# HCF4051.net
KiCad netlist of a schematic drawn in Altium Designer
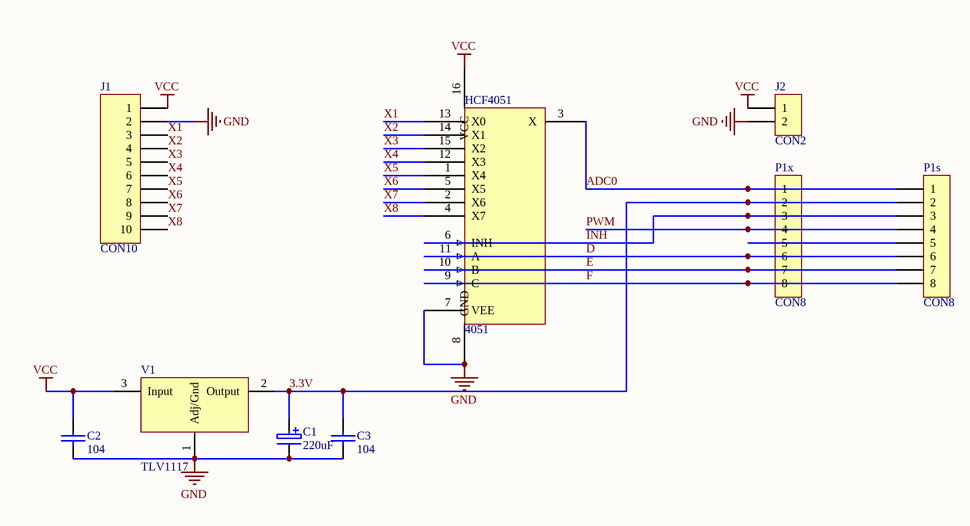
[diagram p0: HCF4051.SchDoc]

(export (version "E")
  (design (tool "Eeschema 10.0.6"))
  (components
    (comp (ref "C1") (value "220uF") (footprint "CAO1") (libsource (lib "C电容") (part "CAP3")))
    (comp (ref "C2") (value "104") (footprint "C0805") (libsource (lib "C电容") (part "CAP1")))
    (comp (ref "C3") (value "104") (footprint "C0805") (libsource (lib "C电容") (part "CAP1")))
    (comp (ref "HCF4051") (value "4051") (footprint "SOP-16") (libsource (lib "4000 CMOS") (part "4051")))
    (comp (ref "J1")
      (value "CON10")
      (footprint "sip-10")
      (description "Connector")
      (libsource (lib "接口") (part "CON10"))
    )
    (comp (ref "J2")
      (value "CON2")
      (footprint "sip-2")
      (description "Connector")
      (libsource (lib "接口") (part "CON2"))
    )
    (comp (ref "P1s")
      (value "CON8")
      (footprint "sip-8")
      (description "Connector")
      (libsource (lib "接口") (part "CON8"))
    )
    (comp (ref "P1x")
      (value "CON8")
      (footprint "sip-8")
      (description "Connector")
      (libsource (lib "接口") (part "CON8"))
    )
    (comp (ref "V1") (value "TLV1117") (footprint "SOT-223") (libsource (lib "Voltage电压基准") (part "TLV1117")))
  )
  (nets
    (net (code "1") (name "/3.3V") (class "Default")
      (node (ref "C1") (pin "1") (pintype "passive"))
      (node (ref "C3") (pin "2") (pinfunction "2_2") (pintype "passive"))
      (node (ref "P1s") (pin "2") (pinfunction "2_2") (pintype "passive"))
      (node (ref "P1x") (pin "2") (pinfunction "2_2") (pintype "passive"))
      (node (ref "V1") (pin "2") (pinfunction "Output_2") (pintype "passive"))
    )
    (net (code "2") (name "/ADC0") (class "Default")
      (node (ref "HCF4051") (pin "3") (pinfunction "X_3") (pintype "passive"))
      (node (ref "P1s") (pin "1") (pinfunction "1_1") (pintype "passive"))
      (node (ref "P1x") (pin "1") (pinfunction "1_1") (pintype "passive"))
    )
    (net (code "3") (name "/D") (class "Default")
      (node (ref "HCF4051") (pin "11") (pinfunction "A_11") (pintype "input"))
      (node (ref "P1s") (pin "6") (pinfunction "6_6") (pintype "passive"))
      (node (ref "P1x") (pin "6") (pinfunction "6_6") (pintype "passive"))
    )
    (net (code "4") (name "/E") (class "Default")
      (node (ref "HCF4051") (pin "10") (pinfunction "B_10") (pintype "input"))
      (node (ref "P1s") (pin "7") (pinfunction "7_7") (pintype "passive"))
      (node (ref "P1x") (pin "7") (pinfunction "7_7") (pintype "passive"))
    )
    (net (code "5") (name "/F") (class "Default")
      (node (ref "HCF4051") (pin "9") (pinfunction "C_9") (pintype "input"))
      (node (ref "P1s") (pin "8") (pinfunction "8_8") (pintype "passive"))
      (node (ref "P1x") (pin "8") (pinfunction "8_8") (pintype "passive"))
    )
    (net (code "6") (name "/INH") (class "Default")
      (node (ref "HCF4051") (pin "6") (pinfunction "INH_6") (pintype "input"))
      (node (ref "P1s") (pin "3") (pinfunction "3_3") (pintype "passive"))
      (node (ref "P1x") (pin "3") (pinfunction "3_3") (pintype "passive"))
    )
    (net (code "7") (name "/PWM") (class "Default")
      (node (ref "P1s") (pin "4") (pinfunction "4_4") (pintype "passive"))
      (node (ref "P1x") (pin "4") (pinfunction "4_4") (pintype "passive"))
    )
    (net (code "8") (name "/X1") (class "Default")
      (node (ref "HCF4051") (pin "13") (pinfunction "X0_13") (pintype "passive"))
      (node (ref "J1") (pin "3") (pinfunction "3_3") (pintype "passive"))
    )
    (net (code "9") (name "/X2") (class "Default")
      (node (ref "HCF4051") (pin "14") (pinfunction "X1_14") (pintype "passive"))
      (node (ref "J1") (pin "4") (pinfunction "4_4") (pintype "passive"))
    )
    (net (code "10") (name "/X3") (class "Default")
      (node (ref "HCF4051") (pin "15") (pinfunction "X2_15") (pintype "passive"))
      (node (ref "J1") (pin "5") (pinfunction "5_5") (pintype "passive"))
    )
    (net (code "11") (name "/X4") (class "Default")
      (node (ref "HCF4051") (pin "12") (pinfunction "X3_12") (pintype "passive"))
      (node (ref "J1") (pin "6") (pinfunction "6_6") (pintype "passive"))
    )
    (net (code "12") (name "/X5") (class "Default")
      (node (ref "HCF4051") (pin "1") (pinfunction "X4_1") (pintype "passive"))
      (node (ref "J1") (pin "7") (pinfunction "7_7") (pintype "passive"))
    )
    (net (code "13") (name "/X6") (class "Default")
      (node (ref "HCF4051") (pin "5") (pinfunction "X5_5") (pintype "passive"))
      (node (ref "J1") (pin "8") (pinfunction "8_8") (pintype "passive"))
    )
    (net (code "14") (name "/X7") (class "Default")
      (node (ref "HCF4051") (pin "2") (pinfunction "X6_2") (pintype "passive"))
      (node (ref "J1") (pin "9") (pinfunction "9_9") (pintype "passive"))
    )
    (net (code "15") (name "/X8") (class "Default")
      (node (ref "HCF4051") (pin "4") (pinfunction "X7_4") (pintype "passive"))
      (node (ref "J1") (pin "10") (pinfunction "10_10") (pintype "passive"))
    )
    (net (code "16") (name "GND") (class "Default")
      (node (ref "C1") (pin "2") (pintype "passive"))
      (node (ref "C2") (pin "1") (pinfunction "1_1") (pintype "passive"))
      (node (ref "C3") (pin "1") (pinfunction "1_1") (pintype "passive"))
      (node (ref "HCF4051") (pin "7") (pinfunction "VEE_7") (pintype "passive"))
      (node (ref "HCF4051") (pin "8") (pinfunction "GND_8") (pintype "power_in"))
      (node (ref "J1") (pin "2") (pinfunction "2_2") (pintype "passive"))
      (node (ref "J2") (pin "2") (pinfunction "2_2") (pintype "passive"))
      (node (ref "V1") (pin "1") (pinfunction "Adj/Gnd_1") (pintype "passive"))
    )
    (net (code "17") (name "Net-(P1s-Pad5)") (class "Default")
      (node (ref "P1s") (pin "5") (pinfunction "5_5") (pintype "passive"))
      (node (ref "P1x") (pin "5") (pinfunction "5_5") (pintype "passive"))
    )
    (net (code "18") (name "VCC") (class "Default")
      (node (ref "C2") (pin "2") (pinfunction "2_2") (pintype "passive"))
      (node (ref "HCF4051") (pin "16") (pinfunction "VCC_16") (pintype "power_in"))
      (node (ref "J1") (pin "1") (pinfunction "1_1") (pintype "passive"))
      (node (ref "J2") (pin "1") (pinfunction "1_1") (pintype "passive"))
      (node (ref "V1") (pin "3") (pinfunction "Input_3") (pintype "passive"))
    )
  )
)
